# arduino_pro_mini.net
KiCad netlist of a schematic drawn in EAGLE
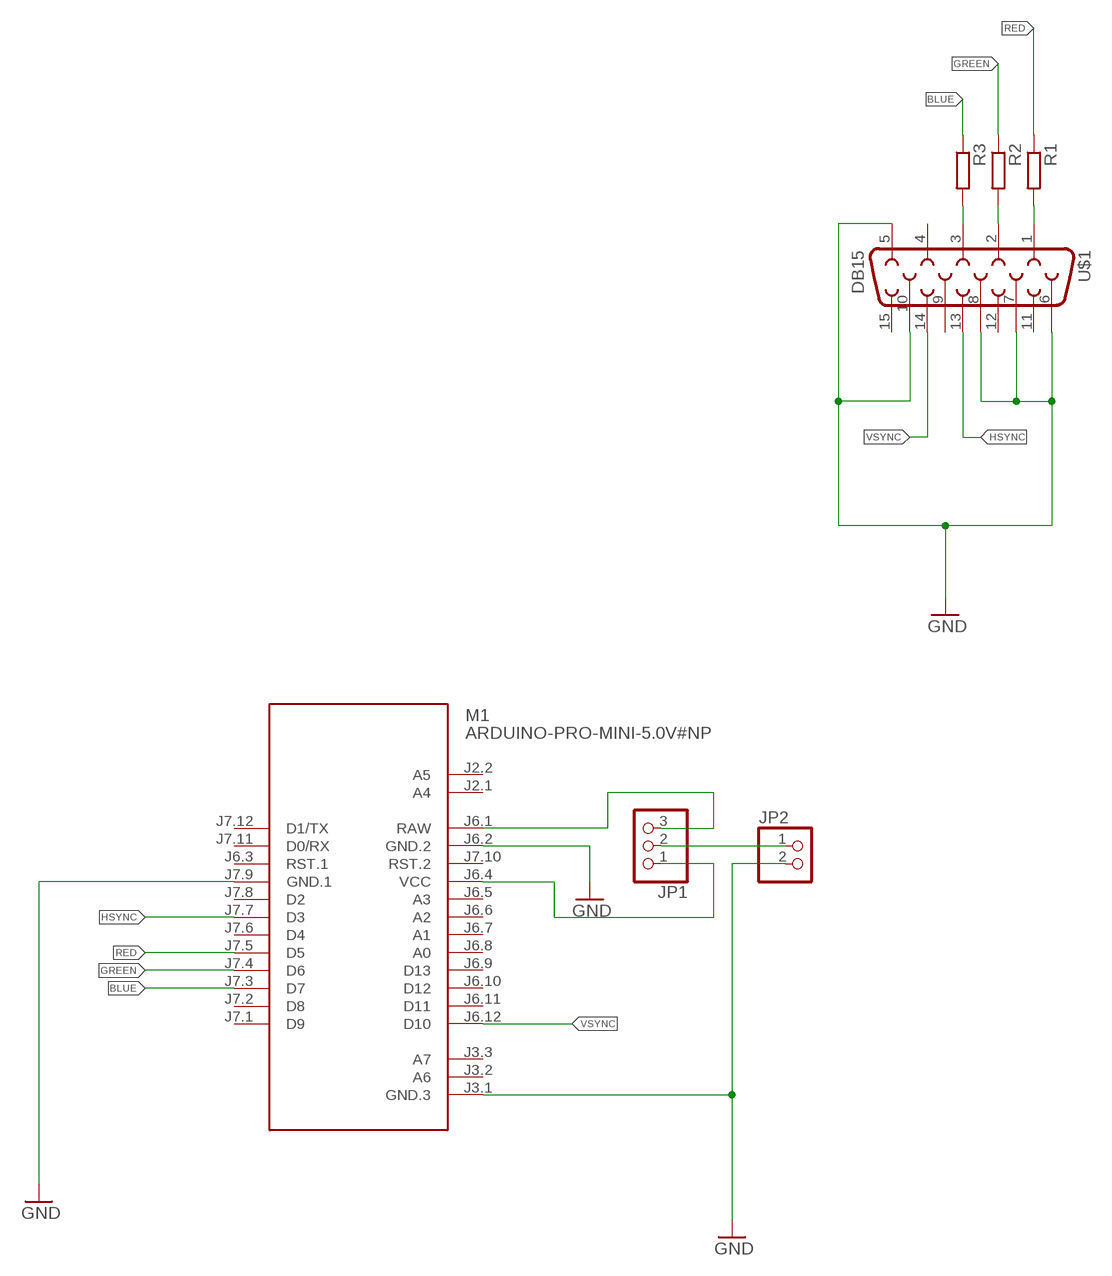
[diagram p0: schematic, sheet 1]

(export (version "E")
  (design (tool "Eeschema 10.0.6"))
  (components
    (comp (ref "JP1")
      (value "PINHD-1X3/90")
      (footprint "eagle-import:1X03_90")
      (libsource (lib "eagle-import") (part "PINHD-1X3/90"))
    )
    (comp (ref "JP2")
      (value "PINHD-1X2")
      (footprint "eagle-import:1X02")
      (libsource (lib "eagle-import") (part "PINHD-1X2"))
    )
    (comp (ref "M1")
      (value "ARDUINO-PRO-MINI-5.0V#NP")
      (footprint "eagle-import:ARDUINO-PRO-MINI#NP")
      (libsource (lib "eagle-import") (part "ARDUINO-PRO-MINI-#NP5.0V"))
    )
    (comp (ref "R1")
      (value "R-EU_0207/10")
      (footprint "eagle-import:0207_10")
      (libsource (lib "eagle-import") (part "R-EU_0207/10"))
    )
    (comp (ref "R2")
      (value "R-EU_0207/10")
      (footprint "eagle-import:0207_10")
      (libsource (lib "eagle-import") (part "R-EU_0207/10"))
    )
    (comp (ref "R3")
      (value "R-EU_0207/10")
      (footprint "eagle-import:0207_10")
      (libsource (lib "eagle-import") (part "R-EU_0207/10"))
    )
    (comp (ref "U$1")
      (value "DB15")
      (footprint "eagle-import:DB15")
      (libsource (lib "eagle-import") (part "DB15"))
    )
  )
  (nets
    (net (code "1") (name "BLUE") (class "Default")
      (node (ref "M1") (pin "J7.3") (pinfunction "D7_J7.3") (pintype "bidirectional"))
      (node (ref "R3") (pin "1") (pinfunction "1_1") (pintype "passive"))
    )
    (net (code "2") (name "GND") (class "Default")
      (node (ref "JP2") (pin "2") (pinfunction "2_2") (pintype "passive"))
      (node (ref "M1") (pin "J3.1") (pinfunction "GND.3_J3.1") (pintype "bidirectional"))
      (node (ref "M1") (pin "J6.2") (pinfunction "GND.2_J6.2") (pintype "power_in"))
      (node (ref "M1") (pin "J7.9") (pinfunction "GND.1_J7.9") (pintype "power_in"))
      (node (ref "U$1") (pin "10") (pinfunction "10_10") (pintype "passive"))
      (node (ref "U$1") (pin "5") (pinfunction "5_5") (pintype "passive"))
      (node (ref "U$1") (pin "6") (pinfunction "6_6") (pintype "passive"))
      (node (ref "U$1") (pin "7") (pinfunction "7_7") (pintype "passive"))
      (node (ref "U$1") (pin "8") (pinfunction "8_8") (pintype "passive"))
    )
    (net (code "3") (name "GREEN") (class "Default")
      (node (ref "M1") (pin "J7.4") (pinfunction "D6_J7.4") (pintype "bidirectional"))
      (node (ref "R2") (pin "1") (pinfunction "1_1") (pintype "passive"))
    )
    (net (code "4") (name "HSYNC") (class "Default")
      (node (ref "M1") (pin "J7.7") (pinfunction "D3_J7.7") (pintype "bidirectional"))
      (node (ref "U$1") (pin "13") (pinfunction "13_13") (pintype "passive"))
    )
    (net (code "5") (name "Net-(JP1-Pad2)") (class "Default")
      (node (ref "JP1") (pin "2") (pinfunction "2_2") (pintype "passive"))
      (node (ref "JP2") (pin "1") (pinfunction "1_1") (pintype "passive"))
    )
    (net (code "6") (name "Net-(M1-RAW)") (class "Default")
      (node (ref "JP1") (pin "3") (pinfunction "3_3") (pintype "passive"))
      (node (ref "M1") (pin "J6.1") (pinfunction "RAW_J6.1") (pintype "power_in"))
    )
    (net (code "7") (name "Net-(M1-VCC)") (class "Default")
      (node (ref "JP1") (pin "1") (pinfunction "1_1") (pintype "passive"))
      (node (ref "M1") (pin "J6.4") (pinfunction "VCC_J6.4") (pintype "power_in"))
    )
    (net (code "8") (name "Net-(R1-Pad2)") (class "Default")
      (node (ref "R1") (pin "2") (pinfunction "2_2") (pintype "passive"))
      (node (ref "U$1") (pin "1") (pinfunction "1_1") (pintype "passive"))
    )
    (net (code "9") (name "Net-(R2-Pad2)") (class "Default")
      (node (ref "R2") (pin "2") (pinfunction "2_2") (pintype "passive"))
      (node (ref "U$1") (pin "2") (pinfunction "2_2") (pintype "passive"))
    )
    (net (code "10") (name "Net-(R3-Pad2)") (class "Default")
      (node (ref "R3") (pin "2") (pinfunction "2_2") (pintype "passive"))
      (node (ref "U$1") (pin "3") (pinfunction "3_3") (pintype "passive"))
    )
    (net (code "11") (name "RED") (class "Default")
      (node (ref "M1") (pin "J7.5") (pinfunction "D5_J7.5") (pintype "bidirectional"))
      (node (ref "R1") (pin "1") (pinfunction "1_1") (pintype "passive"))
    )
    (net (code "12") (name "VSYNC") (class "Default")
      (node (ref "M1") (pin "J6.12") (pinfunction "D10_J6.12") (pintype "bidirectional"))
      (node (ref "U$1") (pin "14") (pinfunction "14_14") (pintype "passive"))
    )
    (net (code "13") (name "unconnected-(M1-A0-PadJ6.8)") (class "Default")
      (node (ref "M1") (pin "J6.8") (pinfunction "A0_J6.8") (pintype "bidirectional"))
    )
    (net (code "14") (name "unconnected-(M1-A1-PadJ6.7)") (class "Default")
      (node (ref "M1") (pin "J6.7") (pinfunction "A1_J6.7") (pintype "bidirectional"))
    )
    (net (code "15") (name "unconnected-(M1-A2-PadJ6.6)") (class "Default")
      (node (ref "M1") (pin "J6.6") (pinfunction "A2_J6.6") (pintype "bidirectional"))
    )
    (net (code "16") (name "unconnected-(M1-A3-PadJ6.5)") (class "Default")
      (node (ref "M1") (pin "J6.5") (pinfunction "A3_J6.5") (pintype "bidirectional"))
    )
    (net (code "17") (name "unconnected-(M1-A4-PadJ2.1)") (class "Default")
      (node (ref "M1") (pin "J2.1") (pinfunction "A4_J2.1") (pintype "bidirectional"))
    )
    (net (code "18") (name "unconnected-(M1-A5-PadJ2.2)") (class "Default")
      (node (ref "M1") (pin "J2.2") (pinfunction "A5_J2.2") (pintype "bidirectional"))
    )
    (net (code "19") (name "unconnected-(M1-A6-PadJ3.2)") (class "Default")
      (node (ref "M1") (pin "J3.2") (pinfunction "A6_J3.2") (pintype "bidirectional"))
    )
    (net (code "20") (name "unconnected-(M1-A7-PadJ3.3)") (class "Default")
      (node (ref "M1") (pin "J3.3") (pinfunction "A7_J3.3") (pintype "bidirectional"))
    )
    (net (code "21") (name "unconnected-(M1-D0{slash}RX-PadJ7.11)") (class "Default")
      (node (ref "M1") (pin "J7.11") (pinfunction "D0/RX_J7.11") (pintype "bidirectional"))
    )
    (net (code "22") (name "unconnected-(M1-D1{slash}TX-PadJ7.12)") (class "Default")
      (node (ref "M1") (pin "J7.12") (pinfunction "D1/TX_J7.12") (pintype "bidirectional"))
    )
    (net (code "23") (name "unconnected-(M1-D2-PadJ7.8)") (class "Default")
      (node (ref "M1") (pin "J7.8") (pinfunction "D2_J7.8") (pintype "bidirectional"))
    )
    (net (code "24") (name "unconnected-(M1-D4-PadJ7.6)") (class "Default")
      (node (ref "M1") (pin "J7.6") (pinfunction "D4_J7.6") (pintype "bidirectional"))
    )
    (net (code "25") (name "unconnected-(M1-D8-PadJ7.2)") (class "Default")
      (node (ref "M1") (pin "J7.2") (pinfunction "D8_J7.2") (pintype "bidirectional"))
    )
    (net (code "26") (name "unconnected-(M1-D9-PadJ7.1)") (class "Default")
      (node (ref "M1") (pin "J7.1") (pinfunction "D9_J7.1") (pintype "bidirectional"))
    )
    (net (code "27") (name "unconnected-(M1-D11-PadJ6.11)") (class "Default")
      (node (ref "M1") (pin "J6.11") (pinfunction "D11_J6.11") (pintype "bidirectional"))
    )
    (net (code "28") (name "unconnected-(M1-D12-PadJ6.10)") (class "Default")
      (node (ref "M1") (pin "J6.10") (pinfunction "D12_J6.10") (pintype "bidirectional"))
    )
    (net (code "29") (name "unconnected-(M1-D13-PadJ6.9)") (class "Default")
      (node (ref "M1") (pin "J6.9") (pinfunction "D13_J6.9") (pintype "bidirectional"))
    )
    (net (code "30") (name "unconnected-(M1-RST.1-PadJ6.3)") (class "Default")
      (node (ref "M1") (pin "J6.3") (pinfunction "RST.1_J6.3") (pintype "bidirectional"))
    )
    (net (code "31") (name "unconnected-(M1-RST.2-PadJ7.10)") (class "Default")
      (node (ref "M1") (pin "J7.10") (pinfunction "RST.2_J7.10") (pintype "bidirectional"))
    )
    (net (code "32") (name "unconnected-(U$1-Pad4)") (class "Default")
      (node (ref "U$1") (pin "4") (pinfunction "4_4") (pintype "passive"))
    )
    (net (code "33") (name "unconnected-(U$1-Pad9)") (class "Default")
      (node (ref "U$1") (pin "9") (pinfunction "9_9") (pintype "passive"))
    )
    (net (code "34") (name "unconnected-(U$1-Pad11)") (class "Default")
      (node (ref "U$1") (pin "11") (pinfunction "11_11") (pintype "passive"))
    )
    (net (code "35") (name "unconnected-(U$1-Pad12)") (class "Default")
      (node (ref "U$1") (pin "12") (pinfunction "12_12") (pintype "passive"))
    )
    (net (code "36") (name "unconnected-(U$1-Pad15)") (class "Default")
      (node (ref "U$1") (pin "15") (pinfunction "15_15") (pintype "passive"))
    )
  )
)
